# rubidium-osc-sa22c-breakout.net
KiCad netlist of a schematic drawn in EAGLE
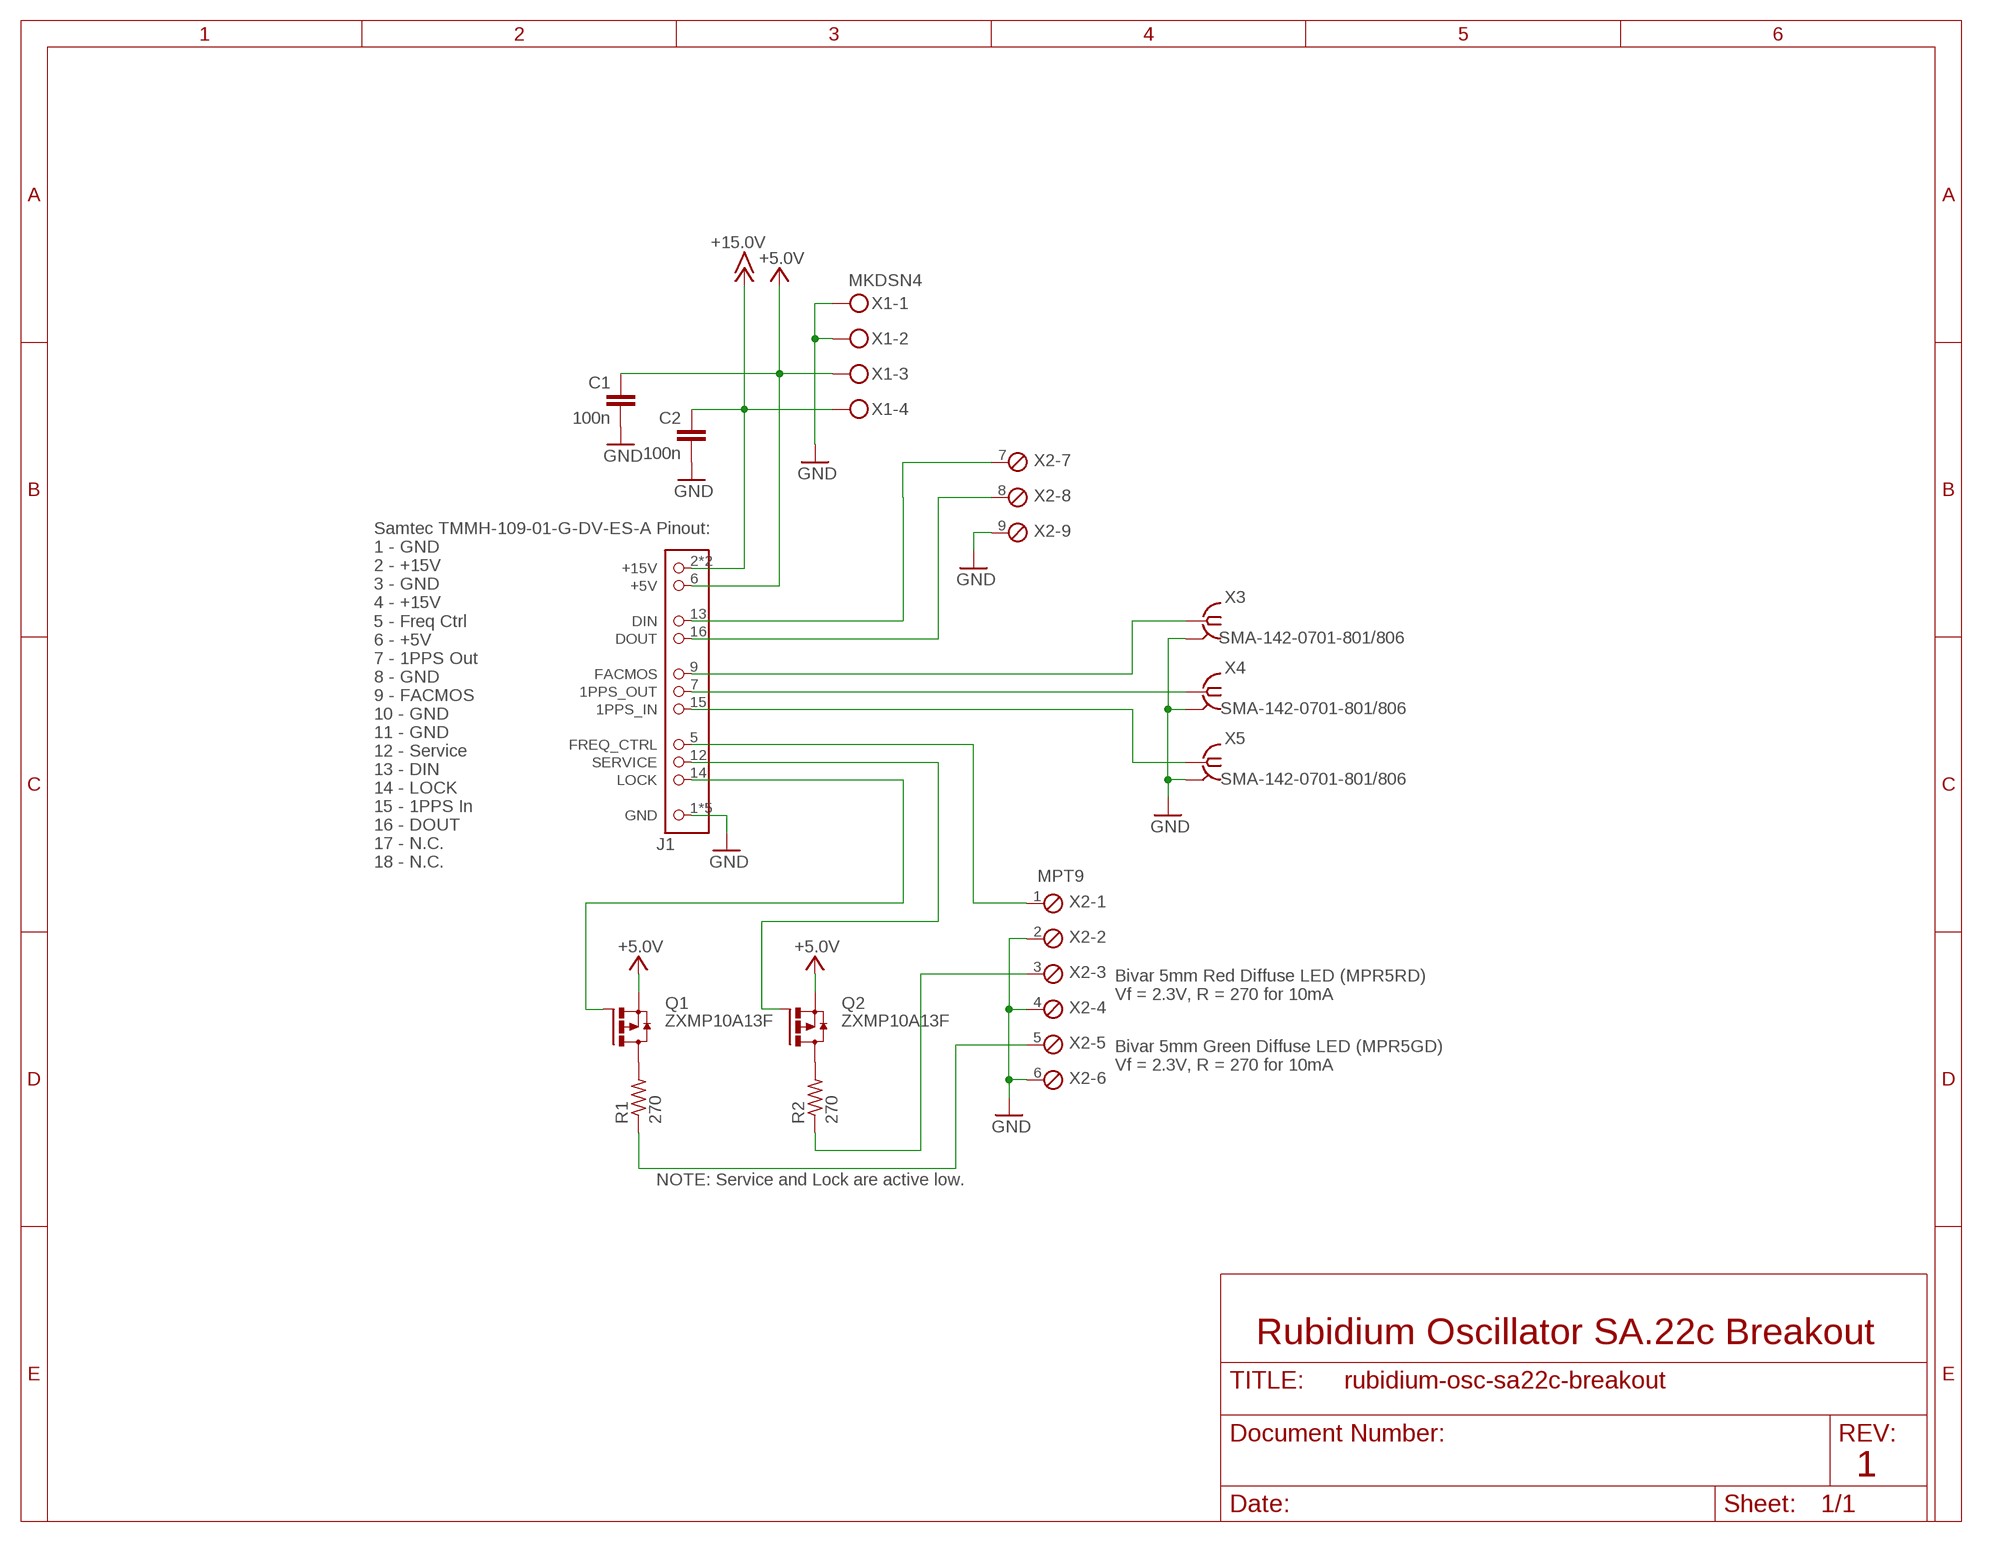
[diagram p0: schematic, sheet 1]

(export (version "E")
  (design (tool "Eeschema 10.0.6"))
  (components
    (comp (ref "C1")
      (value "100n")
      (footprint "eagle-import:C0603")
      (libsource (lib "eagle-import") (part "C-EUC0603"))
    )
    (comp (ref "C2")
      (value "100n")
      (footprint "eagle-import:C0603")
      (libsource (lib "eagle-import") (part "C-EUC0603"))
    )
    (comp (ref "J1")
      (value "OSC_TMMH-109-01-G-DV-ES-A")
      (footprint "eagle-import:TMMH-109-XX-XX-DV-ES-A")
      (libsource (lib "eagle-import") (part "OSC_TMMH-109-01-G-DV-ES-A"))
    )
    (comp (ref "Q1")
      (value "ZXMP10A13F")
      (footprint "eagle-import:SUPER-SOT3")
      (libsource (lib "eagle-import") (part "FDN360P"))
    )
    (comp (ref "Q2")
      (value "ZXMP10A13F")
      (footprint "eagle-import:SUPER-SOT3")
      (libsource (lib "eagle-import") (part "FDN360P"))
    )
    (comp (ref "R1")
      (value "270")
      (footprint "eagle-import:R0603")
      (libsource (lib "eagle-import") (part "R-US_R0603"))
    )
    (comp (ref "R2")
      (value "270")
      (footprint "eagle-import:R0603")
      (libsource (lib "eagle-import") (part "R-US_R0603"))
    )
    (comp (ref "X1")
      (value "MKDSN4")
      (footprint "eagle-import:MKDSN1,5_4-5,08")
      (libsource (lib "eagle-import") (part "MKDSN1,5/4-5,08"))
    )
    (comp (ref "X2")
      (value "MPT9")
      (footprint "eagle-import:9POL254")
      (libsource (lib "eagle-import") (part "MPT9"))
    )
    (comp (ref "X3")
      (value "SMA-142-0701-801/806")
      (footprint "eagle-import:J502-ND-142-0701-801_806")
      (fields (field (name "MF") "JOHNSON COMPONENTS") (field (name "MPN") "142-0701-801"))
      (libsource (lib "eagle-import") (part "SMA-142-0701-801/806"))
    )
    (comp (ref "X4")
      (value "SMA-142-0701-801/806")
      (footprint "eagle-import:J502-ND-142-0701-801_806")
      (fields (field (name "MF") "JOHNSON COMPONENTS") (field (name "MPN") "142-0701-801"))
      (libsource (lib "eagle-import") (part "SMA-142-0701-801/806"))
    )
    (comp (ref "X5")
      (value "SMA-142-0701-801/806")
      (footprint "eagle-import:J502-ND-142-0701-801_806")
      (fields (field (name "MF") "JOHNSON COMPONENTS") (field (name "MPN") "142-0701-801"))
      (libsource (lib "eagle-import") (part "SMA-142-0701-801/806"))
    )
  )
  (nets
    (net (code "1") (name "+5.0V") (class "Default")
      (node (ref "C1") (pin "1") (pinfunction "1_1") (pintype "passive"))
      (node (ref "J1") (pin "6") (pinfunction "+5V_6") (pintype "passive"))
      (node (ref "Q1") (pin "2") (pinfunction "S_2") (pintype "passive"))
      (node (ref "Q2") (pin "2") (pinfunction "S_2") (pintype "passive"))
      (node (ref "X1") (pin "3") (pinfunction "KL_3") (pintype "passive"))
    )
    (net (code "2") (name "+15.0V") (class "Default")
      (node (ref "C2") (pin "1") (pinfunction "1_1") (pintype "passive"))
      (node (ref "J1") (pin "2") (pinfunction "+15V_2") (pintype "passive"))
      (node (ref "J1") (pin "4") (pinfunction "+15V_4") (pintype "passive"))
      (node (ref "X1") (pin "4") (pinfunction "KL_4") (pintype "passive"))
    )
    (net (code "3") (name "GND") (class "Default")
      (node (ref "C1") (pin "2") (pinfunction "2_2") (pintype "passive"))
      (node (ref "C2") (pin "2") (pinfunction "2_2") (pintype "passive"))
      (node (ref "J1") (pin "1") (pinfunction "GND_1") (pintype "passive"))
      (node (ref "J1") (pin "10") (pinfunction "GND_10") (pintype "passive"))
      (node (ref "J1") (pin "11") (pinfunction "GND_11") (pintype "passive"))
      (node (ref "J1") (pin "3") (pinfunction "GND_3") (pintype "passive"))
      (node (ref "J1") (pin "8") (pinfunction "GND_8") (pintype "passive"))
      (node (ref "X1") (pin "1") (pinfunction "KL_1") (pintype "passive"))
      (node (ref "X1") (pin "2") (pinfunction "KL_2") (pintype "passive"))
      (node (ref "X2") (pin "2") (pinfunction "1_2") (pintype "passive"))
      (node (ref "X2") (pin "4") (pinfunction "1_4") (pintype "passive"))
      (node (ref "X2") (pin "6") (pinfunction "1_6") (pintype "passive"))
      (node (ref "X2") (pin "9") (pinfunction "1_9") (pintype "passive"))
      (node (ref "X3") (pin "G@1") (pinfunction "2_G@1") (pintype "passive"))
      (node (ref "X3") (pin "G@2") (pinfunction "2_G@2") (pintype "passive"))
      (node (ref "X3") (pin "G@3") (pinfunction "2_G@3") (pintype "passive"))
      (node (ref "X3") (pin "G@4") (pinfunction "2_G@4") (pintype "passive"))
      (node (ref "X4") (pin "G@1") (pinfunction "2_G@1") (pintype "passive"))
      (node (ref "X4") (pin "G@2") (pinfunction "2_G@2") (pintype "passive"))
      (node (ref "X4") (pin "G@3") (pinfunction "2_G@3") (pintype "passive"))
      (node (ref "X4") (pin "G@4") (pinfunction "2_G@4") (pintype "passive"))
      (node (ref "X5") (pin "G@1") (pinfunction "2_G@1") (pintype "passive"))
      (node (ref "X5") (pin "G@2") (pinfunction "2_G@2") (pintype "passive"))
      (node (ref "X5") (pin "G@3") (pinfunction "2_G@3") (pintype "passive"))
      (node (ref "X5") (pin "G@4") (pinfunction "2_G@4") (pintype "passive"))
    )
    (net (code "4") (name "Net-(J1-1PPS_IN)") (class "Default")
      (node (ref "J1") (pin "15") (pinfunction "1PPS_IN_15") (pintype "passive"))
      (node (ref "X5") (pin "1") (pinfunction "1_1") (pintype "passive"))
    )
    (net (code "5") (name "Net-(J1-1PPS_OUT)") (class "Default")
      (node (ref "J1") (pin "7") (pinfunction "1PPS_OUT_7") (pintype "passive"))
      (node (ref "X4") (pin "1") (pinfunction "1_1") (pintype "passive"))
    )
    (net (code "6") (name "Net-(J1-DIN)") (class "Default")
      (node (ref "J1") (pin "13") (pinfunction "DIN_13") (pintype "passive"))
      (node (ref "X2") (pin "7") (pinfunction "1_7") (pintype "passive"))
    )
    (net (code "7") (name "Net-(J1-DOUT)") (class "Default")
      (node (ref "J1") (pin "16") (pinfunction "DOUT_16") (pintype "passive"))
      (node (ref "X2") (pin "8") (pinfunction "1_8") (pintype "passive"))
    )
    (net (code "8") (name "Net-(J1-FACMOS)") (class "Default")
      (node (ref "J1") (pin "9") (pinfunction "FACMOS_9") (pintype "passive"))
      (node (ref "X3") (pin "1") (pinfunction "1_1") (pintype "passive"))
    )
    (net (code "9") (name "Net-(J1-FREQ_CTRL)") (class "Default")
      (node (ref "J1") (pin "5") (pinfunction "FREQ_CTRL_5") (pintype "passive"))
      (node (ref "X2") (pin "1") (pinfunction "1_1") (pintype "passive"))
    )
    (net (code "10") (name "Net-(J1-LOCK)") (class "Default")
      (node (ref "J1") (pin "14") (pinfunction "LOCK_14") (pintype "passive"))
      (node (ref "Q1") (pin "1") (pinfunction "G_1") (pintype "passive"))
    )
    (net (code "11") (name "Net-(J1-SERVICE)") (class "Default")
      (node (ref "J1") (pin "12") (pinfunction "SERVICE_12") (pintype "passive"))
      (node (ref "Q2") (pin "1") (pinfunction "G_1") (pintype "passive"))
    )
    (net (code "12") (name "Net-(Q1-D)") (class "Default")
      (node (ref "Q1") (pin "3") (pinfunction "D_3") (pintype "passive"))
      (node (ref "R1") (pin "2") (pinfunction "2_2") (pintype "passive"))
    )
    (net (code "13") (name "Net-(Q2-D)") (class "Default")
      (node (ref "Q2") (pin "3") (pinfunction "D_3") (pintype "passive"))
      (node (ref "R2") (pin "2") (pinfunction "2_2") (pintype "passive"))
    )
    (net (code "14") (name "Net-(X2C-1)") (class "Default")
      (node (ref "R2") (pin "1") (pinfunction "1_1") (pintype "passive"))
      (node (ref "X2") (pin "3") (pinfunction "1_3") (pintype "passive"))
    )
    (net (code "15") (name "Net-(X2E-1)") (class "Default")
      (node (ref "R1") (pin "1") (pinfunction "1_1") (pintype "passive"))
      (node (ref "X2") (pin "5") (pinfunction "1_5") (pintype "passive"))
    )
  )
)
